# servo-breakout.net
KiCad netlist of a schematic drawn in EAGLE
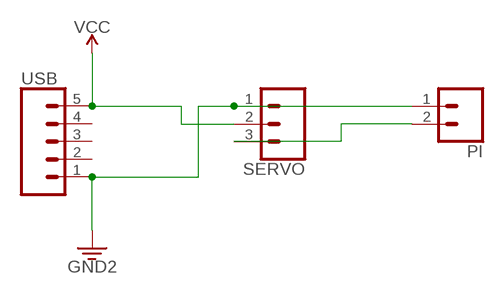
[diagram p0: schematic, sheet 1]

(export (version "E")
  (design (tool "Eeschema 10.0.6"))
  (components
    (comp (ref "PI")
      (value "CONN_021X02_NO_SILK")
      (footprint "eagle-import:1X02_NO_SILK")
      (libsource (lib "eagle-import") (part "CONN_021X02_NO_SILK"))
    )
    (comp (ref "SERVO")
      (value "CONN_031X03_NO_SILK")
      (footprint "eagle-import:1X03_NO_SILK")
      (libsource (lib "eagle-import") (part "CONN_031X03_NO_SILK"))
    )
    (comp (ref "USB")
      (value "CONN_05NO_SILK")
      (footprint "eagle-import:1X05_NO_SILK")
      (libsource (lib "eagle-import") (part "CONN_05NO_SILK"))
    )
  )
  (nets
    (net (code "1") (name "GND2") (class "Default")
      (node (ref "PI") (pin "1") (pinfunction "1_1") (pintype "passive"))
      (node (ref "SERVO") (pin "1") (pinfunction "1_1") (pintype "passive"))
      (node (ref "USB") (pin "1") (pinfunction "1_1") (pintype "passive"))
    )
    (net (code "2") (name "Net-(PI-Pad2)") (class "Default")
      (node (ref "PI") (pin "2") (pinfunction "2_2") (pintype "passive"))
      (node (ref "SERVO") (pin "3") (pinfunction "3_3") (pintype "passive"))
    )
    (net (code "3") (name "VCC") (class "Default")
      (node (ref "SERVO") (pin "2") (pinfunction "2_2") (pintype "passive"))
      (node (ref "USB") (pin "5") (pinfunction "5_5") (pintype "passive"))
    )
    (net (code "4") (name "unconnected-(USB-Pad2)") (class "Default")
      (node (ref "USB") (pin "2") (pinfunction "2_2") (pintype "passive"))
    )
    (net (code "5") (name "unconnected-(USB-Pad3)") (class "Default")
      (node (ref "USB") (pin "3") (pinfunction "3_3") (pintype "passive"))
    )
    (net (code "6") (name "unconnected-(USB-Pad4)") (class "Default")
      (node (ref "USB") (pin "4") (pinfunction "4_4") (pintype "passive"))
    )
  )
)
